# Mainboard_MCU_Breakout.net
KiCad netlist of a schematic drawn in Altium Designer
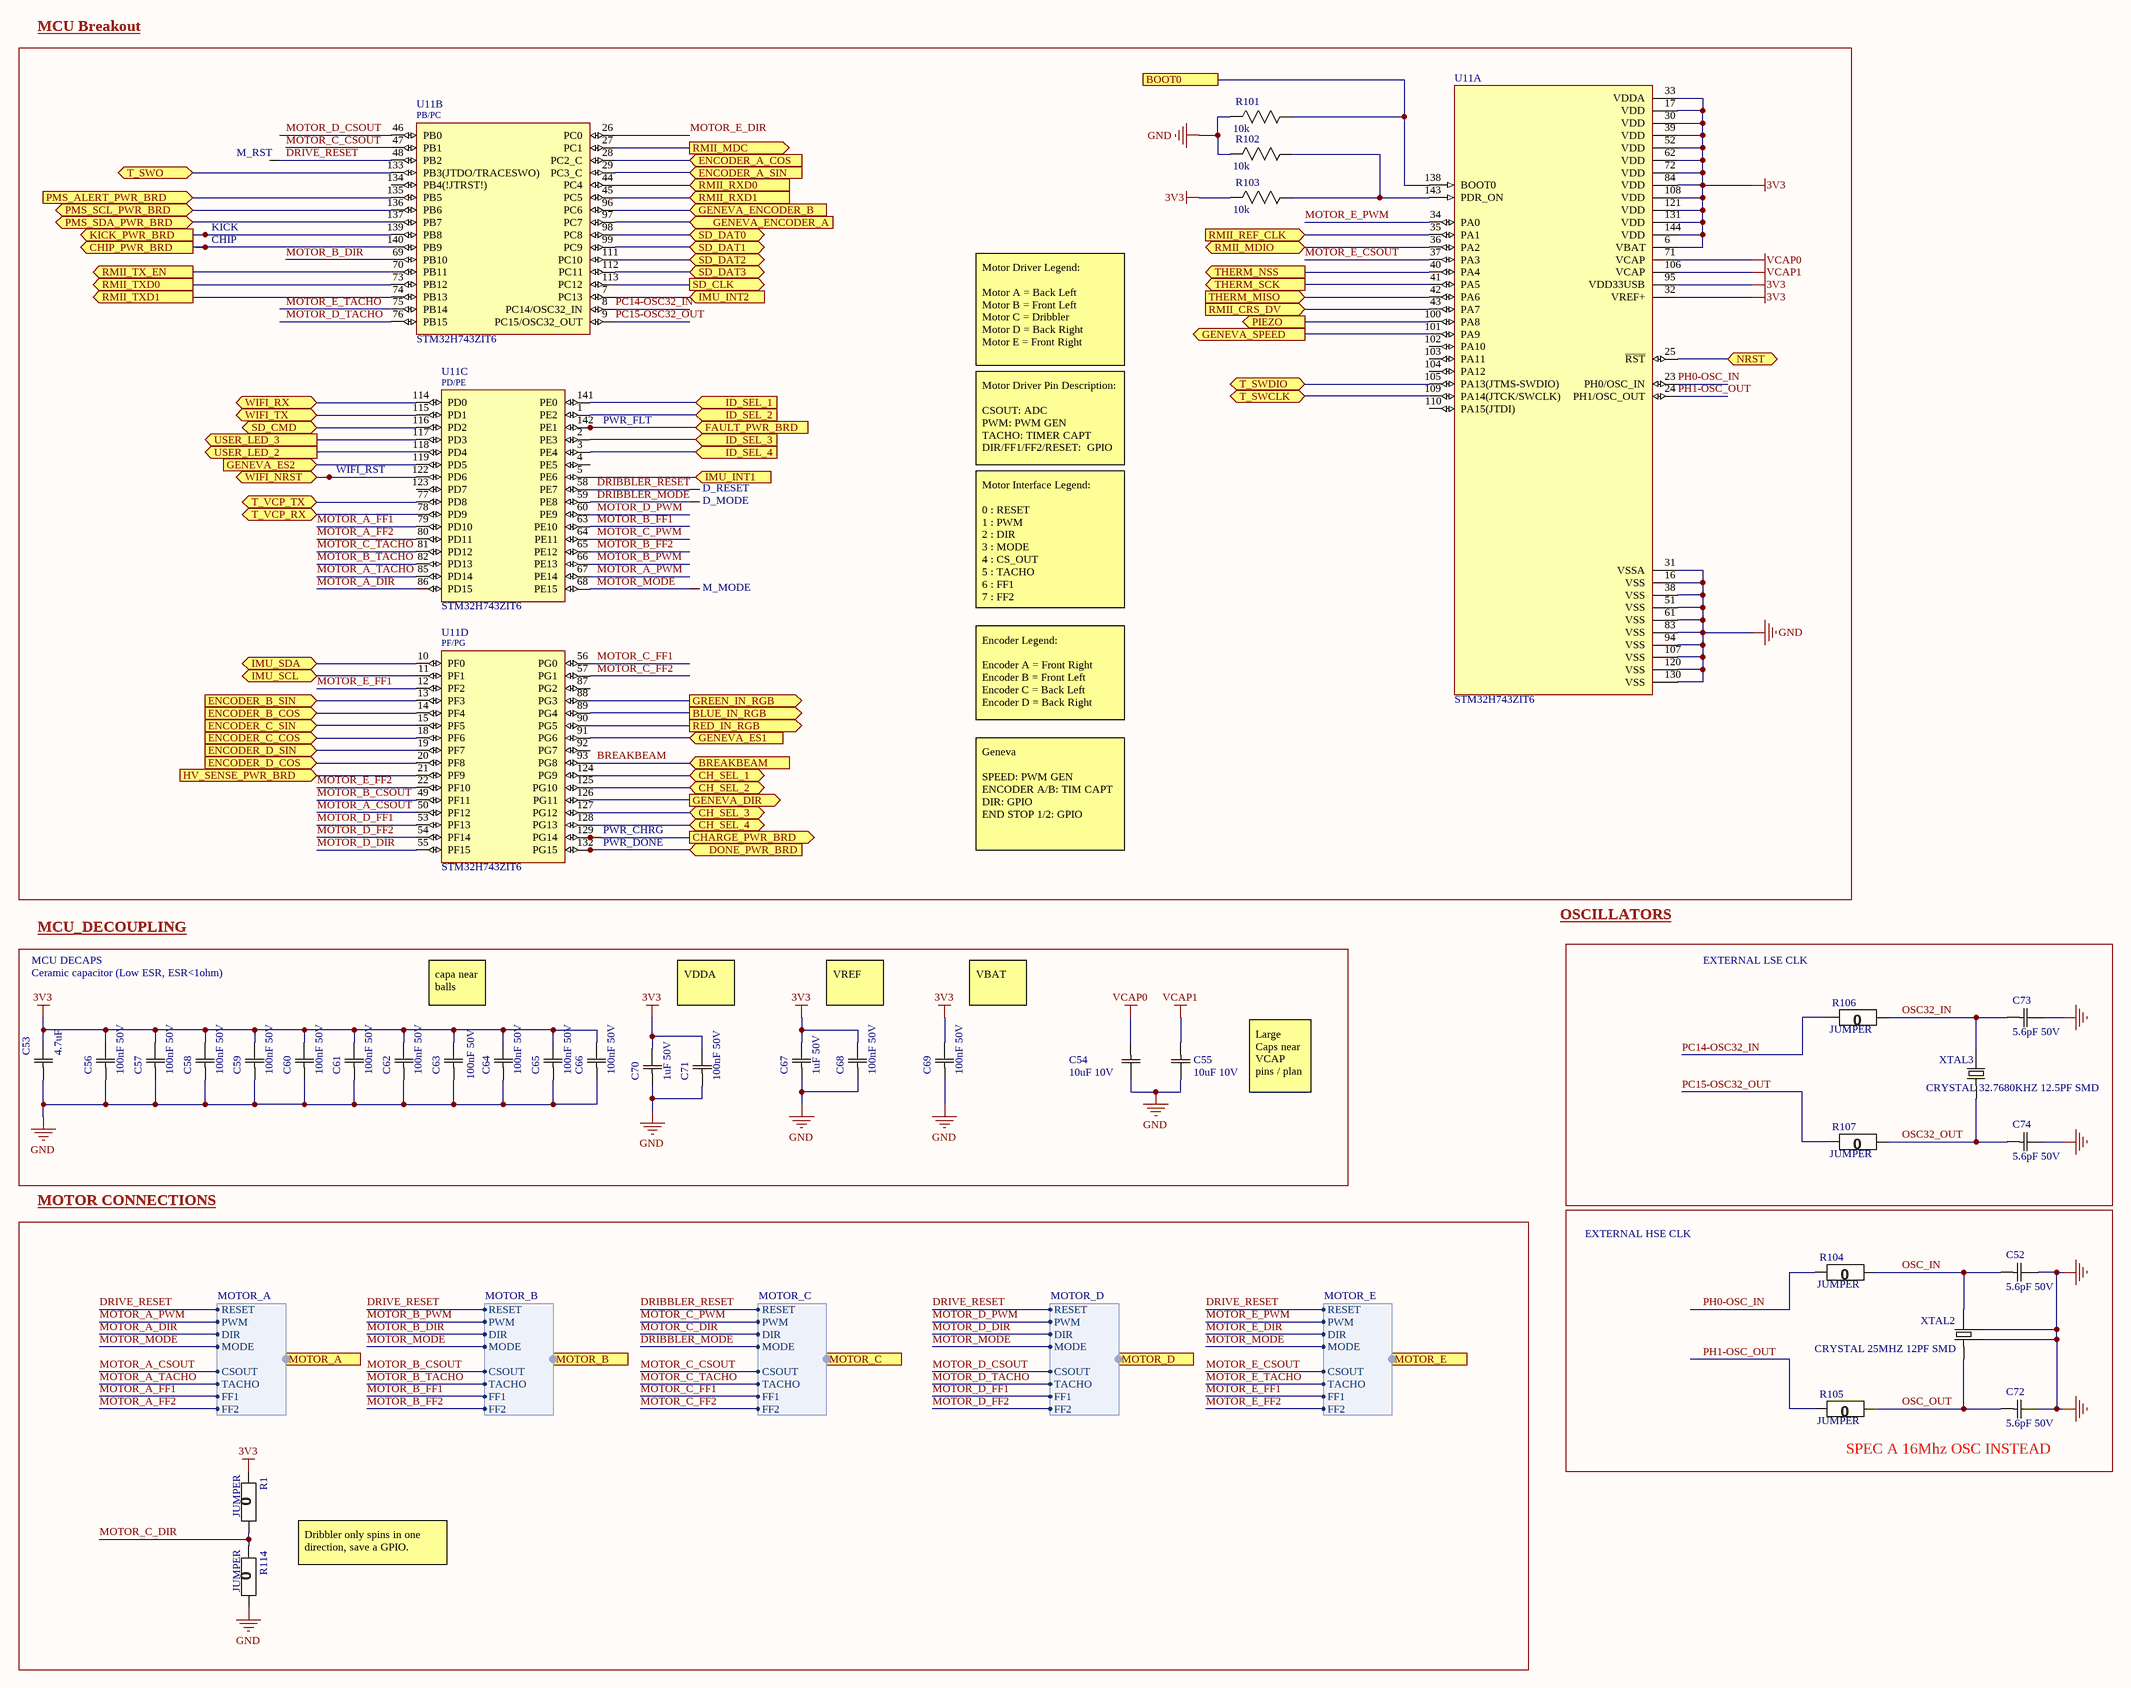
[diagram p0: Mainboard_MCU_Breakout.SchDoc]

(export (version "E")
  (design (tool "Eeschema 10.0.6"))
  (components
    (comp (ref "C52")
      (value "5.6pF 50V")
      (footprint "0603")
      (description "CAP CER 5.6PF 50V C0G/NP0 0805")
      (fields (field (name "TOLERANCE") "5%"))
      (libsource (lib "AltiumLibraries") (part "CAP 5.6pF 50V"))
    )
    (comp (ref "C53")
      (value "4.7uF")
      (footprint "0603")
      (description "CAP CER 4.7UF 35V X7R 0603/0805")
      (fields (field (name "TOLERANCE") "10%"))
      (libsource (lib "AltiumLibraries") (part "CAP 4.7uF 35V"))
    )
    (comp (ref "C54")
      (value "10uF 10V")
      (footprint "0603")
      (description "CAP CER 10UF 10V X5R 0805")
      (fields (field (name "TOLERANCE") "10%"))
      (libsource (lib "AltiumLibraries") (part "CAP 10uF 10V"))
    )
    (comp (ref "C55")
      (value "10uF 10V")
      (footprint "0603")
      (description "CAP CER 10UF 10V X5R 0805")
      (fields (field (name "TOLERANCE") "10%"))
      (libsource (lib "AltiumLibraries") (part "CAP 10uF 10V"))
    )
    (comp (ref "C56")
      (value "100nF 50V")
      (footprint "0603")
      (description "CAP CER 0.1UF 50V X7R 0805")
      (fields (field (name "TOLERANCE") "10%"))
      (libsource (lib "AltiumLibraries") (part "CAP 100nF 50V"))
    )
    (comp (ref "C57")
      (value "100nF 50V")
      (footprint "0603")
      (description "CAP CER 0.1UF 50V X7R 0805")
      (fields (field (name "TOLERANCE") "10%"))
      (libsource (lib "AltiumLibraries") (part "CAP 100nF 50V"))
    )
    (comp (ref "C58")
      (value "100nF 50V")
      (footprint "0603")
      (description "CAP CER 0.1UF 50V X7R 0805")
      (fields (field (name "TOLERANCE") "10%"))
      (libsource (lib "AltiumLibraries") (part "CAP 100nF 50V"))
    )
    (comp (ref "C59")
      (value "100nF 50V")
      (footprint "0603")
      (description "CAP CER 0.1UF 50V X7R 0805")
      (fields (field (name "TOLERANCE") "10%"))
      (libsource (lib "AltiumLibraries") (part "CAP 100nF 50V"))
    )
    (comp (ref "C60")
      (value "100nF 50V")
      (footprint "0603")
      (description "CAP CER 0.1UF 50V X7R 0805")
      (fields (field (name "TOLERANCE") "10%"))
      (libsource (lib "AltiumLibraries") (part "CAP 100nF 50V"))
    )
    (comp (ref "C61")
      (value "100nF 50V")
      (footprint "0603")
      (description "CAP CER 0.1UF 50V X7R 0805")
      (fields (field (name "TOLERANCE") "10%"))
      (libsource (lib "AltiumLibraries") (part "CAP 100nF 50V"))
    )
    (comp (ref "C62")
      (value "100nF 50V")
      (footprint "0603")
      (description "CAP CER 0.1UF 50V X7R 0805")
      (fields (field (name "TOLERANCE") "10%"))
      (libsource (lib "AltiumLibraries") (part "CAP 100nF 50V"))
    )
    (comp (ref "C63")
      (value "100nF 50V")
      (footprint "0603")
      (description "CAP CER 0.1UF 50V X7R 0805")
      (fields (field (name "TOLERANCE") "10%"))
      (libsource (lib "AltiumLibraries") (part "CAP 100nF 50V"))
    )
    (comp (ref "C64")
      (value "100nF 50V")
      (footprint "0603")
      (description "CAP CER 0.1UF 50V X7R 0805")
      (fields (field (name "TOLERANCE") "10%"))
      (libsource (lib "AltiumLibraries") (part "CAP 100nF 50V"))
    )
    (comp (ref "C65")
      (value "100nF 50V")
      (footprint "0603")
      (description "CAP CER 0.1UF 50V X7R 0805")
      (fields (field (name "TOLERANCE") "10%"))
      (libsource (lib "AltiumLibraries") (part "CAP 100nF 50V"))
    )
    (comp (ref "C66")
      (value "100nF 50V")
      (footprint "0603")
      (description "CAP CER 0.1UF 50V X7R 0805")
      (fields (field (name "TOLERANCE") "10%"))
      (libsource (lib "AltiumLibraries") (part "CAP 100nF 50V"))
    )
    (comp (ref "C67")
      (value "1uF 50V")
      (footprint "0603")
      (description "CAP CER 1UF 50V X7R 0805")
      (fields (field (name "TOLERANCE") "10%"))
      (libsource (lib "AltiumLibraries") (part "CAP 1uF 50V"))
    )
    (comp (ref "C68")
      (value "100nF 50V")
      (footprint "0603")
      (description "CAP CER 0.1UF 50V X7R 0805")
      (fields (field (name "TOLERANCE") "10%"))
      (libsource (lib "AltiumLibraries") (part "CAP 100nF 50V"))
    )
    (comp (ref "C69")
      (value "100nF 50V")
      (footprint "0603")
      (description "CAP CER 0.1UF 50V X7R 0805")
      (fields (field (name "TOLERANCE") "10%"))
      (libsource (lib "AltiumLibraries") (part "CAP 100nF 50V"))
    )
    (comp (ref "C70")
      (value "1uF 50V")
      (footprint "0603")
      (description "CAP CER 1UF 50V X7R 0805")
      (fields (field (name "TOLERANCE") "10%"))
      (libsource (lib "AltiumLibraries") (part "CAP 1uF 50V"))
    )
    (comp (ref "C71")
      (value "100nF 50V")
      (footprint "0603")
      (description "CAP CER 0.1UF 50V X7R 0805")
      (fields (field (name "TOLERANCE") "10%"))
      (libsource (lib "AltiumLibraries") (part "CAP 100nF 50V"))
    )
    (comp (ref "C72")
      (value "5.6pF 50V")
      (footprint "0603")
      (description "CAP CER 5.6PF 50V C0G/NP0 0805")
      (fields (field (name "TOLERANCE") "5%"))
      (libsource (lib "AltiumLibraries") (part "CAP 5.6pF 50V"))
    )
    (comp (ref "C73")
      (value "5.6pF 50V")
      (footprint "0603")
      (description "CAP CER 5.6PF 50V C0G/NP0 0805")
      (fields (field (name "TOLERANCE") "5%"))
      (libsource (lib "AltiumLibraries") (part "CAP 5.6pF 50V"))
    )
    (comp (ref "C74")
      (value "5.6pF 50V")
      (footprint "0603")
      (description "CAP CER 5.6PF 50V C0G/NP0 0805")
      (fields (field (name "TOLERANCE") "5%"))
      (libsource (lib "AltiumLibraries") (part "CAP 5.6pF 50V"))
    )
    (comp (ref "CHIP")
      (value "Test Point (Via)")
      (footprint "TP")
      (libsource (lib "AltiumLibraries") (part "Test Point (Via)"))
    )
    (comp (ref "D_MODE")
      (value "Test Point (Via)")
      (footprint "TP")
      (libsource (lib "AltiumLibraries") (part "Test Point (Via)"))
    )
    (comp (ref "D_RESET")
      (value "Test Point (Via)")
      (footprint "TP")
      (libsource (lib "AltiumLibraries") (part "Test Point (Via)"))
    )
    (comp (ref "KICK")
      (value "Test Point (Via)")
      (footprint "TP")
      (libsource (lib "AltiumLibraries") (part "Test Point (Via)"))
    )
    (comp (ref "M_MODE")
      (value "Test Point (Via)")
      (footprint "TP")
      (libsource (lib "AltiumLibraries") (part "Test Point (Via)"))
    )
    (comp (ref "M_RST")
      (value "Test Point (Via)")
      (footprint "TP")
      (libsource (lib "AltiumLibraries") (part "Test Point (Via)"))
    )
    (comp (ref "PWR_CHRG")
      (value "Test Point (Via)")
      (footprint "TP")
      (libsource (lib "AltiumLibraries") (part "Test Point (Via)"))
    )
    (comp (ref "PWR_DONE")
      (value "Test Point (Via)")
      (footprint "TP")
      (libsource (lib "AltiumLibraries") (part "Test Point (Via)"))
    )
    (comp (ref "PWR_FLT")
      (value "Test Point (Via)")
      (footprint "TP")
      (libsource (lib "AltiumLibraries") (part "Test Point (Via)"))
    )
    (comp (ref "R1")
      (value "JUMPER")
      (footprint "0603")
      (description "RES SMD 0 OHM JUMPER GENERIC 0805")
      (libsource (lib "AltiumLibraries") (part "RES 0 JUMPER"))
    )
    (comp (ref "R101")
      (value "10k")
      (footprint "0603")
      (description "RES SMD 10K OHM 1% 1/8W 0805")
      (fields (field (name "TOLERANCE") "1%"))
      (libsource (lib "") (part "RES 10k 1/8W - 1%_1"))
    )
    (comp (ref "R102")
      (value "10k")
      (footprint "0603")
      (description "RES SMD 10K OHM 1% 1/8W 0805")
      (fields (field (name "TOLERANCE") "1%"))
      (libsource (lib "AltiumLibraries") (part "RES 10k 1/8W - 1%"))
    )
    (comp (ref "R103")
      (value "10k")
      (footprint "0603")
      (description "RES SMD 10K OHM 1% 1/8W 0805")
      (fields (field (name "TOLERANCE") "1%"))
      (libsource (lib "AltiumLibraries") (part "RES 10k 1/8W - 1%"))
    )
    (comp (ref "R104")
      (value "JUMPER")
      (footprint "0603")
      (description "RES SMD 0 OHM JUMPER GENERIC 0805")
      (libsource (lib "AltiumLibraries") (part "RES 0 JUMPER"))
    )
    (comp (ref "R105")
      (value "JUMPER")
      (footprint "0603")
      (description "RES SMD 0 OHM JUMPER GENERIC 0805")
      (libsource (lib "AltiumLibraries") (part "RES 0 JUMPER"))
    )
    (comp (ref "R106")
      (value "JUMPER")
      (footprint "0603")
      (description "RES SMD 0 OHM JUMPER GENERIC 0805")
      (libsource (lib "AltiumLibraries") (part "RES 0 JUMPER"))
    )
    (comp (ref "R107")
      (value "JUMPER")
      (footprint "0603")
      (description "RES SMD 0 OHM JUMPER GENERIC 0805")
      (libsource (lib "AltiumLibraries") (part "RES 0 JUMPER"))
    )
    (comp (ref "R114")
      (value "JUMPER")
      (footprint "0603")
      (description "RES SMD 0 OHM JUMPER GENERIC 0805")
      (libsource (lib "AltiumLibraries") (part "RES 0 JUMPER"))
    )
    (comp (ref "U11")
      (value "STM32H743ZIT6")
      (footprint "QFP50P2200X2200X160-144N")
      (description "ARM® Cortex®-M7 STM32H7 Microcontroller IC 32-Bit 480MHz 2MB (2M x 8) FLASH 144-LQFP (20x20)")
      (fields (field (name "MF") "STMicroelectronics"))
      (libsource (lib "AltiumLibraries") (part "STM32H743ZIT6"))
    )
    (comp (ref "WIFI_RST")
      (value "Test Point (Via)")
      (footprint "TP")
      (libsource (lib "AltiumLibraries") (part "Test Point (Via)"))
    )
    (comp (ref "XTAL2")
      (value "CRYSTAL 25MHZ 12PF SMD")
      (footprint "3225-4SMD")
      (description "25MHz ±10ppm Crystal 12pF 40 Ohms 2-SMD, No Lead")
      (fields (field (name "MP") "X322525MOB4SI") (field (name "MF") "Yangxing Tech"))
      (libsource (lib "AltiumLibraries") (part "XTAL 25MHZ 12PF SMD4"))
    )
    (comp (ref "XTAL3")
      (value "CRYSTAL 32.7680KHZ 12.5PF SMD")
      (footprint "3215 SMD2")
      (description "32.768kHz ±20ppm Crystal 12.5pF 70 kOhms 3215SMD, No Lead")
      (fields (field (name "MP") "Q13FC1350000400") (field (name "MF") "Seiko Epson"))
      (libsource (lib "AltiumLibraries") (part "XTAL 32.7680KHZ 12.5PF SMD 3215"))
    )
  )
  (nets
    (net (code "6") (name "/BLUE_IN_RGB") (class "Default")
      (node (ref "U11") (pin "89") (pinfunction "PG4_89") (pintype "bidirectional"))
    )
    (net (code "7") (name "/BOOT0") (class "Default")
      (node (ref "R101") (pin "1") (pinfunction "R1_1") (pintype "passive"))
      (node (ref "U11") (pin "138") (pinfunction "BOOT0_138") (pintype "input"))
    )
    (net (code "8") (name "/BREAKBEAM") (class "Default")
      (node (ref "U11") (pin "93") (pinfunction "PG8_93") (pintype "bidirectional"))
    )
    (net (code "9") (name "/CHARGE_PWR_BRD") (class "Default")
      (node (ref "PWR_CHRG") (pin "1") (pinfunction "1_1") (pintype "passive"))
      (node (ref "U11") (pin "129") (pinfunction "PG14_129") (pintype "bidirectional"))
    )
    (net (code "10") (name "/CHIP_PWR_BRD") (class "Default")
      (node (ref "CHIP") (pin "1") (pinfunction "1_1") (pintype "passive"))
      (node (ref "U11") (pin "140") (pinfunction "PB9_140") (pintype "bidirectional"))
    )
    (net (code "11") (name "/CH_SEL_1") (class "Default")
      (node (ref "U11") (pin "124") (pinfunction "PG9_124") (pintype "bidirectional"))
    )
    (net (code "12") (name "/CH_SEL_2") (class "Default")
      (node (ref "U11") (pin "125") (pinfunction "PG10_125") (pintype "bidirectional"))
    )
    (net (code "13") (name "/CH_SEL_3") (class "Default")
      (node (ref "U11") (pin "127") (pinfunction "PG12_127") (pintype "bidirectional"))
    )
    (net (code "14") (name "/CH_SEL_4") (class "Default")
      (node (ref "U11") (pin "128") (pinfunction "PG13_128") (pintype "bidirectional"))
    )
    (net (code "15") (name "/DONE_PWR_BRD") (class "Default")
      (node (ref "PWR_DONE") (pin "1") (pinfunction "1_1") (pintype "passive"))
      (node (ref "U11") (pin "132") (pinfunction "PG15_132") (pintype "bidirectional"))
    )
    (net (code "16") (name "/DRIBBLER_MODE") (class "Default")
      (node (ref "D_MODE") (pin "1") (pinfunction "1_1") (pintype "passive"))
      (node (ref "U11") (pin "59") (pinfunction "PE8_59") (pintype "bidirectional"))
    )
    (net (code "17") (name "/DRIBBLER_RESET") (class "Default")
      (node (ref "D_RESET") (pin "1") (pinfunction "1_1") (pintype "passive"))
      (node (ref "U11") (pin "58") (pinfunction "PE7_58") (pintype "bidirectional"))
    )
    (net (code "18") (name "/DRIVE_RESET") (class "Default")
      (node (ref "M_RST") (pin "1") (pinfunction "1_1") (pintype "passive"))
      (node (ref "U11") (pin "48") (pinfunction "PB2_48") (pintype "bidirectional"))
    )
    (net (code "19") (name "/ENCODER_A_COS") (class "Default")
      (node (ref "U11") (pin "28") (pinfunction "PC2_C_28") (pintype "bidirectional"))
    )
    (net (code "20") (name "/ENCODER_A_SIN") (class "Default")
      (node (ref "U11") (pin "29") (pinfunction "PC3_C_29") (pintype "bidirectional"))
    )
    (net (code "21") (name "/ENCODER_B_COS") (class "Default")
      (node (ref "U11") (pin "14") (pinfunction "PF4_14") (pintype "bidirectional"))
    )
    (net (code "22") (name "/ENCODER_B_SIN") (class "Default")
      (node (ref "U11") (pin "13") (pinfunction "PF3_13") (pintype "bidirectional"))
    )
    (net (code "23") (name "/ENCODER_C_COS") (class "Default")
      (node (ref "U11") (pin "18") (pinfunction "PF6_18") (pintype "bidirectional"))
    )
    (net (code "24") (name "/ENCODER_C_SIN") (class "Default")
      (node (ref "U11") (pin "15") (pinfunction "PF5_15") (pintype "bidirectional"))
    )
    (net (code "25") (name "/ENCODER_D_COS") (class "Default")
      (node (ref "U11") (pin "20") (pinfunction "PF8_20") (pintype "bidirectional"))
    )
    (net (code "26") (name "/ENCODER_D_SIN") (class "Default")
      (node (ref "U11") (pin "19") (pinfunction "PF7_19") (pintype "bidirectional"))
    )
    (net (code "27") (name "/FAULT_PWR_BRD") (class "Default")
      (node (ref "PWR_FLT") (pin "1") (pinfunction "1_1") (pintype "passive"))
      (node (ref "U11") (pin "142") (pinfunction "PE1_142") (pintype "bidirectional"))
    )
    (net (code "28") (name "/GENEVA_DIR") (class "Default")
      (node (ref "U11") (pin "126") (pinfunction "PG11_126") (pintype "bidirectional"))
    )
    (net (code "29") (name "/GENEVA_ENCODER_A") (class "Default")
      (node (ref "U11") (pin "97") (pinfunction "PC7_97") (pintype "bidirectional"))
    )
    (net (code "30") (name "/GENEVA_ENCODER_B") (class "Default")
      (node (ref "U11") (pin "96") (pinfunction "PC6_96") (pintype "bidirectional"))
    )
    (net (code "31") (name "/GENEVA_ES1") (class "Default")
      (node (ref "U11") (pin "91") (pinfunction "PG6_91") (pintype "bidirectional"))
    )
    (net (code "32") (name "/GENEVA_ES2") (class "Default")
      (node (ref "U11") (pin "119") (pinfunction "PD5_119") (pintype "bidirectional"))
    )
    (net (code "33") (name "/GENEVA_SPEED") (class "Default")
      (node (ref "U11") (pin "101") (pinfunction "PA9_101") (pintype "bidirectional"))
    )
    (net (code "34") (name "/GREEN_IN_RGB") (class "Default")
      (node (ref "U11") (pin "88") (pinfunction "PG3_88") (pintype "bidirectional"))
    )
    (net (code "35") (name "/HV_SENSE_PWR_BRD") (class "Default")
      (node (ref "U11") (pin "21") (pinfunction "PF9_21") (pintype "bidirectional"))
    )
    (net (code "36") (name "/ID_SEL_1") (class "Default")
      (node (ref "U11") (pin "141") (pinfunction "PE0_141") (pintype "bidirectional"))
    )
    (net (code "37") (name "/ID_SEL_2") (class "Default")
      (node (ref "U11") (pin "1") (pinfunction "PE2_1") (pintype "bidirectional"))
    )
    (net (code "38") (name "/ID_SEL_3") (class "Default")
      (node (ref "U11") (pin "2") (pinfunction "PE3_2") (pintype "bidirectional"))
    )
    (net (code "39") (name "/ID_SEL_4") (class "Default")
      (node (ref "U11") (pin "3") (pinfunction "PE4_3") (pintype "bidirectional"))
    )
    (net (code "40") (name "/IMU_INT1") (class "Default")
      (node (ref "U11") (pin "5") (pinfunction "PE6_5") (pintype "bidirectional"))
    )
    (net (code "41") (name "/IMU_INT2") (class "Default")
      (node (ref "U11") (pin "7") (pinfunction "PC13_7") (pintype "bidirectional"))
    )
    (net (code "42") (name "/IMU_SCL") (class "Default")
      (node (ref "U11") (pin "11") (pinfunction "PF1_11") (pintype "bidirectional"))
    )
    (net (code "43") (name "/IMU_SDA") (class "Default")
      (node (ref "U11") (pin "10") (pinfunction "PF0_10") (pintype "bidirectional"))
    )
    (net (code "44") (name "/KICK_PWR_BRD") (class "Default")
      (node (ref "KICK") (pin "1") (pinfunction "1_1") (pintype "passive"))
      (node (ref "U11") (pin "139") (pinfunction "PB8_139") (pintype "bidirectional"))
    )
    (net (code "45") (name "/MOTOR_A_CSOUT") (class "Default")
      (node (ref "U11") (pin "50") (pinfunction "PF12_50") (pintype "bidirectional"))
    )
    (net (code "46") (name "/MOTOR_A_DIR") (class "Default")
      (node (ref "U11") (pin "86") (pinfunction "PD15_86") (pintype "bidirectional"))
    )
    (net (code "47") (name "/MOTOR_A_FF1") (class "Default")
      (node (ref "U11") (pin "79") (pinfunction "PD10_79") (pintype "bidirectional"))
    )
    (net (code "48") (name "/MOTOR_A_FF2") (class "Default")
      (node (ref "U11") (pin "80") (pinfunction "PD11_80") (pintype "bidirectional"))
    )
    (net (code "49") (name "/MOTOR_A_PWM") (class "Default")
      (node (ref "U11") (pin "67") (pinfunction "PE14_67") (pintype "bidirectional"))
    )
    (net (code "50") (name "/MOTOR_A_TACHO") (class "Default")
      (node (ref "U11") (pin "85") (pinfunction "PD14_85") (pintype "bidirectional"))
    )
    (net (code "51") (name "/MOTOR_B_CSOUT") (class "Default")
      (node (ref "U11") (pin "49") (pinfunction "PF11_49") (pintype "bidirectional"))
    )
    (net (code "52") (name "/MOTOR_B_DIR") (class "Default")
      (node (ref "U11") (pin "69") (pinfunction "PB10_69") (pintype "bidirectional"))
    )
    (net (code "53") (name "/MOTOR_B_FF1") (class "Default")
      (node (ref "U11") (pin "63") (pinfunction "PE10_63") (pintype "bidirectional"))
    )
    (net (code "54") (name "/MOTOR_B_FF2") (class "Default")
      (node (ref "U11") (pin "65") (pinfunction "PE12_65") (pintype "bidirectional"))
    )
    (net (code "55") (name "/MOTOR_B_PWM") (class "Default")
      (node (ref "U11") (pin "66") (pinfunction "PE13_66") (pintype "bidirectional"))
    )
    (net (code "56") (name "/MOTOR_B_TACHO") (class "Default")
      (node (ref "U11") (pin "82") (pinfunction "PD13_82") (pintype "bidirectional"))
    )
    (net (code "57") (name "/MOTOR_C_CSOUT") (class "Default")
      (node (ref "U11") (pin "47") (pinfunction "PB1_47") (pintype "bidirectional"))
    )
    (net (code "58") (name "/MOTOR_C_DIR") (class "Default")
      (node (ref "R1") (pin "1") (pinfunction "R1_1") (pintype "passive"))
      (node (ref "R114") (pin "2") (pinfunction "R2_2") (pintype "passive"))
    )
    (net (code "59") (name "/MOTOR_C_FF1") (class "Default")
      (node (ref "U11") (pin "56") (pinfunction "PG0_56") (pintype "bidirectional"))
    )
    (net (code "60") (name "/MOTOR_C_FF2") (class "Default")
      (node (ref "U11") (pin "57") (pinfunction "PG1_57") (pintype "bidirectional"))
    )
    (net (code "61") (name "/MOTOR_C_PWM") (class "Default")
      (node (ref "U11") (pin "64") (pinfunction "PE11_64") (pintype "bidirectional"))
    )
    (net (code "62") (name "/MOTOR_C_TACHO") (class "Default")
      (node (ref "U11") (pin "81") (pinfunction "PD12_81") (pintype "bidirectional"))
    )
    (net (code "63") (name "/MOTOR_D_CSOUT") (class "Default")
      (node (ref "U11") (pin "46") (pinfunction "PB0_46") (pintype "bidirectional"))
    )
    (net (code "64") (name "/MOTOR_D_DIR") (class "Default")
      (node (ref "U11") (pin "55") (pinfunction "PF15_55") (pintype "bidirectional"))
    )
    (net (code "65") (name "/MOTOR_D_FF1") (class "Default")
      (node (ref "U11") (pin "53") (pinfunction "PF13_53") (pintype "bidirectional"))
    )
    (net (code "66") (name "/MOTOR_D_FF2") (class "Default")
      (node (ref "U11") (pin "54") (pinfunction "PF14_54") (pintype "bidirectional"))
    )
    (net (code "67") (name "/MOTOR_D_PWM") (class "Default")
      (node (ref "U11") (pin "60") (pinfunction "PE9_60") (pintype "bidirectional"))
    )
    (net (code "68") (name "/MOTOR_D_TACHO") (class "Default")
      (node (ref "U11") (pin "76") (pinfunction "PB15_76") (pintype "bidirectional"))
    )
    (net (code "69") (name "/MOTOR_E_CSOUT") (class "Default")
      (node (ref "U11") (pin "37") (pinfunction "PA3_37") (pintype "bidirectional"))
    )
    (net (code "70") (name "/MOTOR_E_DIR") (class "Default")
      (node (ref "U11") (pin "26") (pinfunction "PC0_26") (pintype "bidirectional"))
    )
    (net (code "71") (name "/MOTOR_E_FF1") (class "Default")
      (node (ref "U11") (pin "12") (pinfunction "PF2_12") (pintype "bidirectional"))
    )
    (net (code "72") (name "/MOTOR_E_FF2") (class "Default")
      (node (ref "U11") (pin "22") (pinfunction "PF10_22") (pintype "bidirectional"))
    )
    (net (code "73") (name "/MOTOR_E_PWM") (class "Default")
      (node (ref "U11") (pin "34") (pinfunction "PA0_34") (pintype "bidirectional"))
    )
    (net (code "74") (name "/MOTOR_E_TACHO") (class "Default")
      (node (ref "U11") (pin "75") (pinfunction "PB14_75") (pintype "bidirectional"))
    )
    (net (code "75") (name "/MOTOR_MODE") (class "Default")
      (node (ref "M_MODE") (pin "1") (pinfunction "1_1") (pintype "passive"))
      (node (ref "U11") (pin "68") (pinfunction "PE15_68") (pintype "bidirectional"))
    )
    (net (code "76") (name "/NRST") (class "Default")
      (node (ref "U11") (pin "25") (pinfunction "~{RST}_25") (pintype "bidirectional"))
    )
    (net (code "77") (name "/OSC32_IN") (class "Default")
      (node (ref "C73") (pin "1") (pinfunction "C1_1") (pintype "passive"))
      (node (ref "R106") (pin "1") (pinfunction "R1_1") (pintype "passive"))
      (node (ref "XTAL3") (pin "2") (pinfunction "2_2") (pintype "passive"))
    )
    (net (code "78") (name "/OSC32_OUT") (class "Default")
      (node (ref "C74") (pin "1") (pinfunction "C1_1") (pintype "passive"))
      (node (ref "R107") (pin "1") (pinfunction "R1_1") (pintype "passive"))
      (node (ref "XTAL3") (pin "1") (pinfunction "1_1") (pintype "passive"))
    )
    (net (code "79") (name "/OSC_IN") (class "Default")
      (node (ref "C52") (pin "1") (pinfunction "C1_1") (pintype "passive"))
      (node (ref "R104") (pin "1") (pinfunction "R1_1") (pintype "passive"))
      (node (ref "XTAL2") (pin "3") (pinfunction "3_3") (pintype "passive"))
    )
    (net (code "80") (name "/OSC_OUT") (class "Default")
      (node (ref "C72") (pin "1") (pinfunction "C1_1") (pintype "passive"))
      (node (ref "R105") (pin "1") (pinfunction "R1_1") (pintype "passive"))
      (node (ref "XTAL2") (pin "1") (pinfunction "1_1") (pintype "passive"))
    )
    (net (code "81") (name "/PC14-OSC32_IN") (class "Default")
      (node (ref "R106") (pin "2") (pinfunction "R2_2") (pintype "passive"))
      (node (ref "U11") (pin "8") (pinfunction "PC14/OSC32_IN_8") (pintype "bidirectional"))
    )
    (net (code "82") (name "/PC15-OSC32_OUT") (class "Default")
      (node (ref "R107") (pin "2") (pinfunction "R2_2") (pintype "passive"))
      (node (ref "U11") (pin "9") (pinfunction "PC15/OSC32_OUT_9") (pintype "bidirectional"))
    )
    (net (code "83") (name "/PH0-OSC_IN") (class "Default")
      (node (ref "R104") (pin "2") (pinfunction "R2_2") (pintype "passive"))
      (node (ref "U11") (pin "23") (pinfunction "PH0/OSC_IN_23") (pintype "bidirectional"))
    )
    (net (code "84") (name "/PH1-OSC_OUT") (class "Default")
      (node (ref "R105") (pin "2") (pinfunction "R2_2") (pintype "passive"))
      (node (ref "U11") (pin "24") (pinfunction "PH1/OSC_OUT_24") (pintype "bidirectional"))
    )
    (net (code "85") (name "/PIEZO") (class "Default")
      (node (ref "U11") (pin "100") (pinfunction "PA8_100") (pintype "bidirectional"))
    )
    (net (code "86") (name "/PMS_ALERT_PWR_BRD") (class "Default")
      (node (ref "U11") (pin "135") (pinfunction "PB5_135") (pintype "bidirectional"))
    )
    (net (code "87") (name "/PMS_SCL_PWR_BRD") (class "Default")
      (node (ref "U11") (pin "136") (pinfunction "PB6_136") (pintype "bidirectional"))
    )
    (net (code "88") (name "/PMS_SDA_PWR_BRD") (class "Default")
      (node (ref "U11") (pin "137") (pinfunction "PB7_137") (pintype "bidirectional"))
    )
    (net (code "89") (name "/RED_IN_RGB") (class "Default")
      (node (ref "U11") (pin "90") (pinfunction "PG5_90") (pintype "bidirectional"))
    )
    (net (code "90") (name "/RMII_CRS_DV") (class "Default")
      (node (ref "U11") (pin "43") (pinfunction "PA7_43") (pintype "bidirectional"))
    )
    (net (code "91") (name "/RMII_MDC") (class "Default")
      (node (ref "U11") (pin "27") (pinfunction "PC1_27") (pintype "bidirectional"))
    )
    (net (code "92") (name "/RMII_MDIO") (class "Default")
      (node (ref "U11") (pin "36") (pinfunction "PA2_36") (pintype "bidirectional"))
    )
    (net (code "93") (name "/RMII_REF_CLK") (class "Default")
      (node (ref "U11") (pin "35") (pinfunction "PA1_35") (pintype "bidirectional"))
    )
    (net (code "94") (name "/RMII_RXD0") (class "Default")
      (node (ref "U11") (pin "44") (pinfunction "PC4_44") (pintype "bidirectional"))
    )
    (net (code "95") (name "/RMII_RXD1") (class "Default")
      (node (ref "U11") (pin "45") (pinfunction "PC5_45") (pintype "bidirectional"))
    )
    (net (code "96") (name "/RMII_TXD0") (class "Default")
      (node (ref "U11") (pin "73") (pinfunction "PB12_73") (pintype "bidirectional"))
    )
    (net (code "97") (name "/RMII_TXD1") (class "Default")
      (node (ref "U11") (pin "74") (pinfunction "PB13_74") (pintype "bidirectional"))
    )
    (net (code "98") (name "/RMII_TX_EN") (class "Default")
      (node (ref "U11") (pin "70") (pinfunction "PB11_70") (pintype "bidirectional"))
    )
    (net (code "99") (name "/SD_CLK") (class "Default")
      (node (ref "U11") (pin "113") (pinfunction "PC12_113") (pintype "bidirectional"))
    )
    (net (code "100") (name "/SD_CMD") (class "Default")
      (node (ref "U11") (pin "116") (pinfunction "PD2_116") (pintype "bidirectional"))
    )
    (net (code "101") (name "/SD_DAT0") (class "Default")
      (node (ref "U11") (pin "98") (pinfunction "PC8_98") (pintype "bidirectional"))
    )
    (net (code "102") (name "/SD_DAT1") (class "Default")
      (node (ref "U11") (pin "99") (pinfunction "PC9_99") (pintype "bidirectional"))
    )
    (net (code "103") (name "/SD_DAT2") (class "Default")
      (node (ref "U11") (pin "111") (pinfunction "PC10_111") (pintype "bidirectional"))
    )
    (net (code "104") (name "/SD_DAT3") (class "Default")
      (node (ref "U11") (pin "112") (pinfunction "PC11_112") (pintype "bidirectional"))
    )
    (net (code "105") (name "/THERM_MISO") (class "Default")
      (node (ref "U11") (pin "42") (pinfunction "PA6_42") (pintype "bidirectional"))
    )
    (net (code "106") (name "/THERM_NSS") (class "Default")
      (node (ref "U11") (pin "40") (pinfunction "PA4_40") (pintype "bidirectional"))
    )
    (net (code "107") (name "/THERM_SCK") (class "Default")
      (node (ref "U11") (pin "41") (pinfunction "PA5_41") (pintype "bidirectional"))
    )
    (net (code "108") (name "/T_SWCLK") (class "Default")
      (node (ref "U11") (pin "109") (pinfunction "PA14(JTCK/SWCLK)_109") (pintype "bidirectional"))
    )
    (net (code "109") (name "/T_SWDIO") (class "Default")
      (node (ref "U11") (pin "105") (pinfunction "PA13(JTMS-SWDIO)_105") (pintype "bidirectional"))
    )
    (net (code "110") (name "/T_SWO") (class "Default")
      (node (ref "U11") (pin "133") (pinfunction "PB3(JTDO/TRACESWO)_133") (pintype "bidirectional"))
    )
    (net (code "111") (name "/T_VCP_RX") (class "Default")
      (node (ref "U11") (pin "78") (pinfunction "PD9_78") (pintype "bidirectional"))
    )
    (net (code "112") (name "/T_VCP_TX") (class "Default")
      (node (ref "U11") (pin "77") (pinfunction "PD8_77") (pintype "bidirectional"))
    )
    (net (code "113") (name "/USER_LED_2") (class "Default")
      (node (ref "U11") (pin "118") (pinfunction "PD4_118") (pintype "bidirectional"))
    )
    (net (code "114") (name "/USER_LED_3") (class "Default")
      (node (ref "U11") (pin "117") (pinfunction "PD3_117") (pintype "bidirectional"))
    )
    (net (code "115") (name "/WIFI_NRST") (class "Default")
      (node (ref "U11") (pin "122") (pinfunction "PD6_122") (pintype "bidirectional"))
      (node (ref "WIFI_RST") (pin "1") (pinfunction "1_1") (pintype "passive"))
    )
    (net (code "116") (name "/WIFI_RX") (class "Default")
      (node (ref "U11") (pin "114") (pinfunction "PD0_114") (pintype "bidirectional"))
    )
    (net (code "117") (name "/WIFI_TX") (class "Default")
      (node (ref "U11") (pin "115") (pinfunction "PD1_115") (pintype "bidirectional"))
    )
    (net (code "123") (name "3V3") (class "Default")
      (node (ref "C53") (pin "2") (pinfunction "C2_2") (pintype "passive"))
      (node (ref "C56") (pin "2") (pinfunction "C2_2") (pintype "passive"))
      (node (ref "C57") (pin "2") (pinfunction "C2_2") (pintype "passive"))
      (node (ref "C58") (pin "2") (pinfunction "C2_2") (pintype "passive"))
      (node (ref "C59") (pin "2") (pinfunction "C2_2") (pintype "passive"))
      (node (ref "C60") (pin "2") (pinfunction "C2_2") (pintype "passive"))
      (node (ref "C61") (pin "2") (pinfunction "C2_2") (pintype "passive"))
      (node (ref "C62") (pin "2") (pinfunction "C2_2") (pintype "passive"))
      (node (ref "C63") (pin "2") (pinfunction "C2_2") (pintype "passive"))
      (node (ref "C64") (pin "2") (pinfunction "C2_2") (pintype "passive"))
      (node (ref "C65") (pin "2") (pinfunction "C2_2") (pintype "passive"))
      (node (ref "C66") (pin "2") (pinfunction "C2_2") (pintype "passive"))
      (node (ref "C67") (pin "2") (pinfunction "C2_2") (pintype "passive"))
      (node (ref "C68") (pin "2") (pinfunction "C2_2") (pintype "passive"))
      (node (ref "C69") (pin "2") (pinfunction "C2_2") (pintype "passive"))
      (node (ref "C70") (pin "2") (pinfunction "C2_2") (pintype "passive"))
      (node (ref "C71") (pin "2") (pinfunction "C2_2") (pintype "passive"))
      (node (ref "R1") (pin "2") (pinfunction "R2_2") (pintype "passive"))
      (node (ref "R103") (pin "2") (pinfunction "R2_2") (pintype "passive"))
      (node (ref "U11") (pin "108") (pinfunction "VDD_108") (pintype "power_in"))
      (node (ref "U11") (pin "121") (pinfunction "VDD_121") (pintype "power_in"))
      (node (ref "U11") (pin "131") (pinfunction "VDD_131") (pintype "power_in"))
      (node (ref "U11") (pin "144") (pinfunction "VDD_144") (pintype "power_in"))
      (node (ref "U11") (pin "17") (pinfunction "VDD_17") (pintype "power_in"))
      (node (ref "U11") (pin "30") (pinfunction "VDD_30") (pintype "power_in"))
      (node (ref "U11") (pin "32") (pinfunction "VREF+_32") (pintype "power_in"))
      (node (ref "U11") (pin "33") (pinfunction "VDDA_33") (pintype "power_in"))
      (node (ref "U11") (pin "39") (pinfunction "VDD_39") (pintype "power_in"))
      (node (ref "U11") (pin "52") (pinfunction "VDD_52") (pintype "power_in"))
      (node (ref "U11") (pin "6") (pinfunction "VBAT_6") (pintype "power_in"))
      (node (ref "U11") (pin "62") (pinfunction "VDD_62") (pintype "power_in"))
      (node (ref "U11") (pin "72") (pinfunction "VDD_72") (pintype "power_in"))
      (node (ref "U11") (pin "84") (pinfunction "VDD_84") (pintype "power_in"))
      (node (ref "U11") (pin "95") (pinfunction "VDD33USB_95") (pintype "power_in"))
    )
    (net (code "124") (name "GND") (class "Default")
      (node (ref "C52") (pin "2") (pinfunction "C2_2") (pintype "passive"))
      (node (ref "C53") (pin "1") (pinfunction "C1_1") (pintype "passive"))
      (node (ref "C54") (pin "2") (pinfunction "C2_2") (pintype "passive"))
      (node (ref "C55") (pin "2") (pinfunction "C2_2") (pintype "passive"))
      (node (ref "C56") (pin "1") (pinfunction "C1_1") (pintype "passive"))
      (node (ref "C57") (pin "1") (pinfunction "C1_1") (pintype "passive"))
      (node (ref "C58") (pin "1") (pinfunction "C1_1") (pintype "passive"))
      (node (ref "C59") (pin "1") (pinfunction "C1_1") (pintype "passive"))
      (node (ref "C60") (pin "1") (pinfunction "C1_1") (pintype "passive"))
      (node (ref "C61") (pin "1") (pinfunction "C1_1") (pintype "passive"))
      (node (ref "C62") (pin "1") (pinfunction "C1_1") (pintype "passive"))
      (node (ref "C63") (pin "1") (pinfunction "C1_1") (pintype "passive"))
      (node (ref "C64") (pin "1") (pinfunction "C1_1") (pintype "passive"))
      (node (ref "C65") (pin "1") (pinfunction "C1_1") (pintype "passive"))
      (node (ref "C66") (pin "1") (pinfunction "C1_1") (pintype "passive"))
      (node (ref "C67") (pin "1") (pinfunction "C1_1") (pintype "passive"))
      (node (ref "C68") (pin "1") (pinfunction "C1_1") (pintype "passive"))
      (node (ref "C69") (pin "1") (pinfunction "C1_1") (pintype "passive"))
      (node (ref "C70") (pin "1") (pinfunction "C1_1") (pintype "passive"))
      (node (ref "C71") (pin "1") (pinfunction "C1_1") (pintype "passive"))
      (node (ref "C72") (pin "2") (pinfunction "C2_2") (pintype "passive"))
      (node (ref "C73") (pin "2") (pinfunction "C2_2") (pintype "passive"))
      (node (ref "C74") (pin "2") (pinfunction "C2_2") (pintype "passive"))
      (node (ref "R101") (pin "2") (pinfunction "R2_2") (pintype "passive"))
      (node (ref "R102") (pin "2") (pinfunction "R2_2") (pintype "passive"))
      (node (ref "R114") (pin "1") (pinfunction "R1_1") (pintype "passive"))
      (node (ref "U11") (pin "107") (pinfunction "VSS_107") (pintype "power_in"))
      (node (ref "U11") (pin "120") (pinfunction "VSS_120") (pintype "power_in"))
      (node (ref "U11") (pin "130") (pinfunction "VSS_130") (pintype "power_in"))
      (node (ref "U11") (pin "16") (pinfunction "VSS_16") (pintype "power_in"))
      (node (ref "U11") (pin "31") (pinfunction "VSSA_31") (pintype "power_in"))
      (node (ref "U11") (pin "38") (pinfunction "VSS_38") (pintype "power_in"))
      (node (ref "U11") (pin "51") (pinfunction "VSS_51") (pintype "power_in"))
      (node (ref "U11") (pin "61") (pinfunction "VSS_61") (pintype "power_in"))
      (node (ref "U11") (pin "83") (pinfunction "VSS_83") (pintype "power_in"))
      (node (ref "U11") (pin "94") (pinfunction "VSS_94") (pintype "power_in"))
      (node (ref "XTAL2") (pin "2") (pinfunction "2_2") (pintype "passive"))
      (node (ref "XTAL2") (pin "4") (pinfunction "4_4") (pintype "passive"))
    )
    (net (code "125") (name "Net-(R102-R1)") (class "Default")
      (node (ref "R102") (pin "1") (pinfunction "R1_1") (pintype "passive"))
      (node (ref "R103") (pin "1") (pinfunction "R1_1") (pintype "passive"))
      (node (ref "U11") (pin "143") (pinfunction "PDR_ON_143") (pintype "input"))
    )
    (net (code "126") (name "VCAP0") (class "Default")
      (node (ref "C54") (pin "1") (pinfunction "C1_1") (pintype "passive"))
      (node (ref "U11") (pin "71") (pinfunction "VCAP_71") (pintype "power_in"))
    )
    (net (code "127") (name "VCAP1") (class "Default")
      (node (ref "C55") (pin "1") (pinfunction "C1_1") (pintype "passive"))
      (node (ref "U11") (pin "106") (pinfunction "VCAP_106") (pintype "power_in"))
    )
    (net (code "128") (name "unconnected-(U11A-PA10-Pad102)") (class "Default")
      (node (ref "U11") (pin "102") (pinfunction "PA10_102") (pintype "bidirectional"))
    )
    (net (code "129") (name "unconnected-(U11A-PA11-Pad103)") (class "Default")
      (node (ref "U11") (pin "103") (pinfunction "PA11_103") (pintype "bidirectional"))
    )
    (net (code "130") (name "unconnected-(U11A-PA12-Pad104)") (class "Default")
      (node (ref "U11") (pin "104") (pinfunction "PA12_104") (pintype "bidirectional"))
    )
    (net (code "131") (name "unconnected-(U11A-PA15(JTDI)-Pad110)") (class "Default")
      (node (ref "U11") (pin "110") (pinfunction "PA15(JTDI)_110") (pintype "bidirectional"))
    )
    (net (code "132") (name "unconnected-(U11B-PB4(!JTRST!)-Pad134)") (class "Default")
      (node (ref "U11") (pin "134") (pinfunction "PB4(!JTRST!)_134") (pintype "bidirectional"))
    )
    (net (code "133") (name "unconnected-(U11C-PD7-Pad123)") (class "Default")
      (node (ref "U11") (pin "123") (pinfunction "PD7_123") (pintype "bidirectional"))
    )
    (net (code "134") (name "unconnected-(U11C-PE5-Pad4)") (class "Default")
      (node (ref "U11") (pin "4") (pinfunction "PE5_4") (pintype "bidirectional"))
    )
    (net (code "135") (name "unconnected-(U11D-PG2-Pad87)") (class "Default")
      (node (ref "U11") (pin "87") (pinfunction "PG2_87") (pintype "bidirectional"))
    )
    (net (code "136") (name "unconnected-(U11D-PG7-Pad92)") (class "Default")
      (node (ref "U11") (pin "92") (pinfunction "PG7_92") (pintype "bidirectional"))
    )
  )
)
